# SpaceVNXInterface.net
KiCad netlist of a schematic drawn in Altium Designer
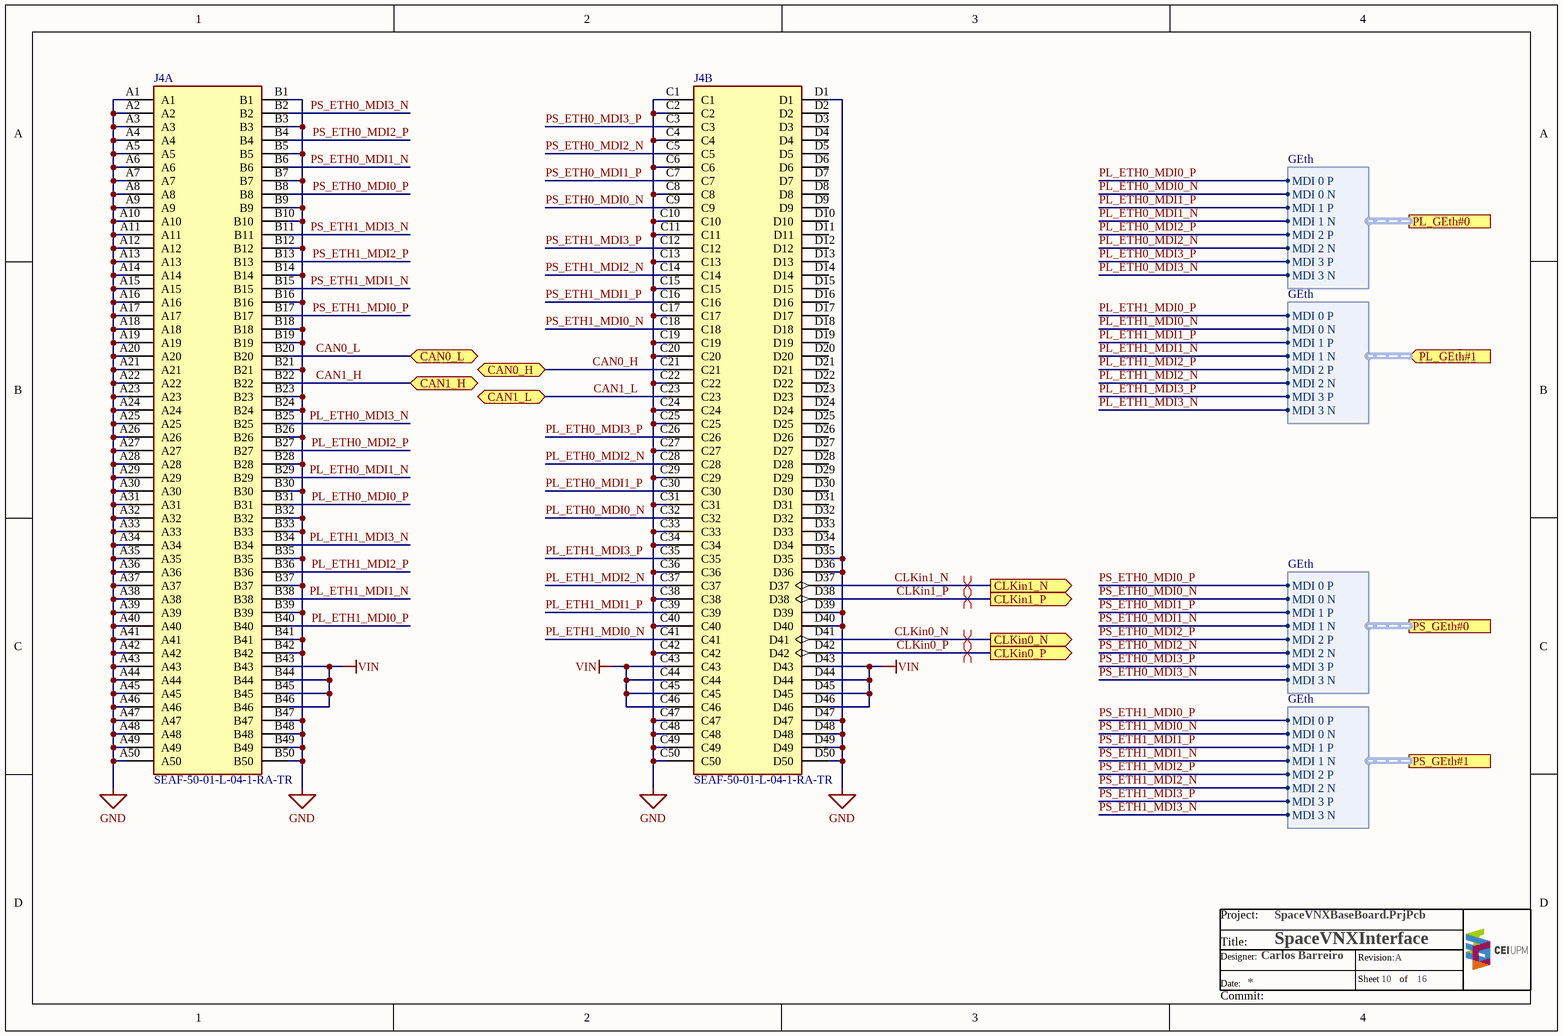
[diagram p0: SpaceVNXInterface.SchDoc]

(export (version "E")
  (design (tool "Eeschema 10.0.6"))
  (components
    (comp (ref "J4")
      (value "SEAF-50-01-L-04-1-RA-TR")
      (footprint "SAMTEC_SEAF-50-01-L-04-1-RA-TR")
      (libsource (lib "SpaceVNX") (part "SEAF-50-01-L-04-1-RA-TR"))
    )
  )
  (nets
    (net (code "2") (name "/CAN0_H") (class "Default")
      (node (ref "J4") (pin "C21") (pinfunction "C21_C21") (pintype "passive"))
    )
    (net (code "3") (name "/CAN0_L") (class "Default")
      (node (ref "J4") (pin "B20") (pinfunction "B20_B20") (pintype "passive"))
    )
    (net (code "4") (name "/CAN1_H") (class "Default")
      (node (ref "J4") (pin "B22") (pinfunction "B22_B22") (pintype "passive"))
    )
    (net (code "5") (name "/CAN1_L") (class "Default")
      (node (ref "J4") (pin "C23") (pinfunction "C23_C23") (pintype "passive"))
    )
    (net (code "6") (name "/CLKin0_N") (class "Default")
      (node (ref "J4") (pin "D41") (pinfunction "D41_D41") (pintype "passive"))
    )
    (net (code "7") (name "/CLKin0_P") (class "Default")
      (node (ref "J4") (pin "D42") (pinfunction "D42_D42") (pintype "passive"))
    )
    (net (code "8") (name "/CLKin1_N") (class "Default")
      (node (ref "J4") (pin "D37") (pinfunction "D37_D37") (pintype "passive"))
    )
    (net (code "9") (name "/CLKin1_P") (class "Default")
      (node (ref "J4") (pin "D38") (pinfunction "D38_D38") (pintype "passive"))
    )
    (net (code "10") (name "/PL_ETH0_MDI0_N") (class "Default")
      (node (ref "J4") (pin "C32") (pinfunction "C32_C32") (pintype "passive"))
    )
    (net (code "11") (name "/PL_ETH0_MDI0_P") (class "Default")
      (node (ref "J4") (pin "B31") (pinfunction "B31_B31") (pintype "passive"))
    )
    (net (code "12") (name "/PL_ETH0_MDI1_N") (class "Default")
      (node (ref "J4") (pin "B29") (pinfunction "B29_B29") (pintype "passive"))
    )
    (net (code "13") (name "/PL_ETH0_MDI1_P") (class "Default")
      (node (ref "J4") (pin "C30") (pinfunction "C30_C30") (pintype "passive"))
    )
    (net (code "14") (name "/PL_ETH0_MDI2_N") (class "Default")
      (node (ref "J4") (pin "C28") (pinfunction "C28_C28") (pintype "passive"))
    )
    (net (code "15") (name "/PL_ETH0_MDI2_P") (class "Default")
      (node (ref "J4") (pin "B27") (pinfunction "B27_B27") (pintype "passive"))
    )
    (net (code "16") (name "/PL_ETH0_MDI3_N") (class "Default")
      (node (ref "J4") (pin "B25") (pinfunction "B25_B25") (pintype "passive"))
    )
    (net (code "17") (name "/PL_ETH0_MDI3_P") (class "Default")
      (node (ref "J4") (pin "C26") (pinfunction "C26_C26") (pintype "passive"))
    )
    (net (code "18") (name "/PL_ETH1_MDI0_N") (class "Default")
      (node (ref "J4") (pin "C41") (pinfunction "C41_C41") (pintype "passive"))
    )
    (net (code "19") (name "/PL_ETH1_MDI0_P") (class "Default")
      (node (ref "J4") (pin "B40") (pinfunction "B40_B40") (pintype "passive"))
    )
    (net (code "20") (name "/PL_ETH1_MDI1_N") (class "Default")
      (node (ref "J4") (pin "B38") (pinfunction "B38_B38") (pintype "passive"))
    )
    (net (code "21") (name "/PL_ETH1_MDI1_P") (class "Default")
      (node (ref "J4") (pin "C39") (pinfunction "C39_C39") (pintype "passive"))
    )
    (net (code "22") (name "/PL_ETH1_MDI2_N") (class "Default")
      (node (ref "J4") (pin "C37") (pinfunction "C37_C37") (pintype "passive"))
    )
    (net (code "23") (name "/PL_ETH1_MDI2_P") (class "Default")
      (node (ref "J4") (pin "B36") (pinfunction "B36_B36") (pintype "passive"))
    )
    (net (code "24") (name "/PL_ETH1_MDI3_N") (class "Default")
      (node (ref "J4") (pin "B34") (pinfunction "B34_B34") (pintype "passive"))
    )
    (net (code "25") (name "/PL_ETH1_MDI3_P") (class "Default")
      (node (ref "J4") (pin "C35") (pinfunction "C35_C35") (pintype "passive"))
    )
    (net (code "26") (name "/PS_ETH0_MDI0_N") (class "Default")
      (node (ref "J4") (pin "C9") (pinfunction "C9_C9") (pintype "passive"))
    )
    (net (code "27") (name "/PS_ETH0_MDI0_P") (class "Default")
      (node (ref "J4") (pin "B8") (pinfunction "B8_B8") (pintype "passive"))
    )
    (net (code "28") (name "/PS_ETH0_MDI1_N") (class "Default")
      (node (ref "J4") (pin "B6") (pinfunction "B6_B6") (pintype "passive"))
    )
    (net (code "29") (name "/PS_ETH0_MDI1_P") (class "Default")
      (node (ref "J4") (pin "C7") (pinfunction "C7_C7") (pintype "passive"))
    )
    (net (code "30") (name "/PS_ETH0_MDI2_N") (class "Default")
      (node (ref "J4") (pin "C5") (pinfunction "C5_C5") (pintype "passive"))
    )
    (net (code "31") (name "/PS_ETH0_MDI2_P") (class "Default")
      (node (ref "J4") (pin "B4") (pinfunction "B4_B4") (pintype "passive"))
    )
    (net (code "32") (name "/PS_ETH0_MDI3_N") (class "Default")
      (node (ref "J4") (pin "B2") (pinfunction "B2_B2") (pintype "passive"))
    )
    (net (code "33") (name "/PS_ETH0_MDI3_P") (class "Default")
      (node (ref "J4") (pin "C3") (pinfunction "C3_C3") (pintype "passive"))
    )
    (net (code "34") (name "/PS_ETH1_MDI0_N") (class "Default")
      (node (ref "J4") (pin "C18") (pinfunction "C18_C18") (pintype "passive"))
    )
    (net (code "35") (name "/PS_ETH1_MDI0_P") (class "Default")
      (node (ref "J4") (pin "B17") (pinfunction "B17_B17") (pintype "passive"))
    )
    (net (code "36") (name "/PS_ETH1_MDI1_N") (class "Default")
      (node (ref "J4") (pin "B15") (pinfunction "B15_B15") (pintype "passive"))
    )
    (net (code "37") (name "/PS_ETH1_MDI1_P") (class "Default")
      (node (ref "J4") (pin "C16") (pinfunction "C16_C16") (pintype "passive"))
    )
    (net (code "38") (name "/PS_ETH1_MDI2_N") (class "Default")
      (node (ref "J4") (pin "C14") (pinfunction "C14_C14") (pintype "passive"))
    )
    (net (code "39") (name "/PS_ETH1_MDI2_P") (class "Default")
      (node (ref "J4") (pin "B13") (pinfunction "B13_B13") (pintype "passive"))
    )
    (net (code "40") (name "/PS_ETH1_MDI3_N") (class "Default")
      (node (ref "J4") (pin "B11") (pinfunction "B11_B11") (pintype "passive"))
    )
    (net (code "41") (name "/PS_ETH1_MDI3_P") (class "Default")
      (node (ref "J4") (pin "C12") (pinfunction "C12_C12") (pintype "passive"))
    )
    (net (code "43") (name "GND") (class "Default")
      (node (ref "J4") (pin "A1") (pinfunction "A1_A1") (pintype "passive"))
      (node (ref "J4") (pin "A10") (pinfunction "A10_A10") (pintype "passive"))
      (node (ref "J4") (pin "A11") (pinfunction "A11_A11") (pintype "passive"))
      (node (ref "J4") (pin "A12") (pinfunction "A12_A12") (pintype "passive"))
      (node (ref "J4") (pin "A13") (pinfunction "A13_A13") (pintype "passive"))
      (node (ref "J4") (pin "A14") (pinfunction "A14_A14") (pintype "passive"))
      (node (ref "J4") (pin "A15") (pinfunction "A15_A15") (pintype "passive"))
      (node (ref "J4") (pin "A16") (pinfunction "A16_A16") (pintype "passive"))
      (node (ref "J4") (pin "A17") (pinfunction "A17_A17") (pintype "passive"))
      (node (ref "J4") (pin "A18") (pinfunction "A18_A18") (pintype "passive"))
      (node (ref "J4") (pin "A19") (pinfunction "A19_A19") (pintype "passive"))
      (node (ref "J4") (pin "A2") (pinfunction "A2_A2") (pintype "passive"))
      (node (ref "J4") (pin "A20") (pinfunction "A20_A20") (pintype "passive"))
      (node (ref "J4") (pin "A21") (pinfunction "A21_A21") (pintype "passive"))
      (node (ref "J4") (pin "A22") (pinfunction "A22_A22") (pintype "passive"))
      (node (ref "J4") (pin "A23") (pinfunction "A23_A23") (pintype "passive"))
      (node (ref "J4") (pin "A24") (pinfunction "A24_A24") (pintype "passive"))
      (node (ref "J4") (pin "A25") (pinfunction "A25_A25") (pintype "passive"))
      (node (ref "J4") (pin "A26") (pinfunction "A26_A26") (pintype "passive"))
      (node (ref "J4") (pin "A27") (pinfunction "A27_A27") (pintype "passive"))
      (node (ref "J4") (pin "A28") (pinfunction "A28_A28") (pintype "passive"))
      (node (ref "J4") (pin "A29") (pinfunction "A29_A29") (pintype "passive"))
      (node (ref "J4") (pin "A3") (pinfunction "A3_A3") (pintype "passive"))
      (node (ref "J4") (pin "A30") (pinfunction "A30_A30") (pintype "passive"))
      (node (ref "J4") (pin "A31") (pinfunction "A31_A31") (pintype "passive"))
      (node (ref "J4") (pin "A32") (pinfunction "A32_A32") (pintype "passive"))
      (node (ref "J4") (pin "A33") (pinfunction "A33_A33") (pintype "passive"))
      (node (ref "J4") (pin "A34") (pinfunction "A34_A34") (pintype "passive"))
      (node (ref "J4") (pin "A35") (pinfunction "A35_A35") (pintype "passive"))
      (node (ref "J4") (pin "A36") (pinfunction "A36_A36") (pintype "passive"))
      (node (ref "J4") (pin "A37") (pinfunction "A37_A37") (pintype "passive"))
      (node (ref "J4") (pin "A38") (pinfunction "A38_A38") (pintype "passive"))
      (node (ref "J4") (pin "A39") (pinfunction "A39_A39") (pintype "passive"))
      (node (ref "J4") (pin "A4") (pinfunction "A4_A4") (pintype "passive"))
      (node (ref "J4") (pin "A40") (pinfunction "A40_A40") (pintype "passive"))
      (node (ref "J4") (pin "A41") (pinfunction "A41_A41") (pintype "passive"))
      (node (ref "J4") (pin "A42") (pinfunction "A42_A42") (pintype "passive"))
      (node (ref "J4") (pin "A43") (pinfunction "A43_A43") (pintype "passive"))
      (node (ref "J4") (pin "A44") (pinfunction "A44_A44") (pintype "passive"))
      (node (ref "J4") (pin "A45") (pinfunction "A45_A45") (pintype "passive"))
      (node (ref "J4") (pin "A46") (pinfunction "A46_A46") (pintype "passive"))
      (node (ref "J4") (pin "A47") (pinfunction "A47_A47") (pintype "passive"))
      (node (ref "J4") (pin "A48") (pinfunction "A48_A48") (pintype "passive"))
      (node (ref "J4") (pin "A49") (pinfunction "A49_A49") (pintype "passive"))
      (node (ref "J4") (pin "A5") (pinfunction "A5_A5") (pintype "passive"))
      (node (ref "J4") (pin "A50") (pinfunction "A50_A50") (pintype "passive"))
      (node (ref "J4") (pin "A6") (pinfunction "A6_A6") (pintype "passive"))
      (node (ref "J4") (pin "A7") (pinfunction "A7_A7") (pintype "passive"))
      (node (ref "J4") (pin "A8") (pinfunction "A8_A8") (pintype "passive"))
      (node (ref "J4") (pin "A9") (pinfunction "A9_A9") (pintype "passive"))
      (node (ref "J4") (pin "B1") (pinfunction "B1_B1") (pintype "passive"))
      (node (ref "J4") (pin "B10") (pinfunction "B10_B10") (pintype "passive"))
      (node (ref "J4") (pin "B12") (pinfunction "B12_B12") (pintype "passive"))
      (node (ref "J4") (pin "B14") (pinfunction "B14_B14") (pintype "passive"))
      (node (ref "J4") (pin "B16") (pinfunction "B16_B16") (pintype "passive"))
      (node (ref "J4") (pin "B18") (pinfunction "B18_B18") (pintype "passive"))
      (node (ref "J4") (pin "B19") (pinfunction "B19_B19") (pintype "passive"))
      (node (ref "J4") (pin "B21") (pinfunction "B21_B21") (pintype "passive"))
      (node (ref "J4") (pin "B23") (pinfunction "B23_B23") (pintype "passive"))
      (node (ref "J4") (pin "B24") (pinfunction "B24_B24") (pintype "passive"))
      (node (ref "J4") (pin "B26") (pinfunction "B26_B26") (pintype "passive"))
      (node (ref "J4") (pin "B28") (pinfunction "B28_B28") (pintype "passive"))
      (node (ref "J4") (pin "B3") (pinfunction "B3_B3") (pintype "passive"))
      (node (ref "J4") (pin "B30") (pinfunction "B30_B30") (pintype "passive"))
      (node (ref "J4") (pin "B32") (pinfunction "B32_B32") (pintype "passive"))
      (node (ref "J4") (pin "B33") (pinfunction "B33_B33") (pintype "passive"))
      (node (ref "J4") (pin "B35") (pinfunction "B35_B35") (pintype "passive"))
      (node (ref "J4") (pin "B37") (pinfunction "B37_B37") (pintype "passive"))
      (node (ref "J4") (pin "B39") (pinfunction "B39_B39") (pintype "passive"))
      (node (ref "J4") (pin "B41") (pinfunction "B41_B41") (pintype "passive"))
      (node (ref "J4") (pin "B42") (pinfunction "B42_B42") (pintype "passive"))
      (node (ref "J4") (pin "B47") (pinfunction "B47_B47") (pintype "passive"))
      (node (ref "J4") (pin "B48") (pinfunction "B48_B48") (pintype "passive"))
      (node (ref "J4") (pin "B49") (pinfunction "B49_B49") (pintype "passive"))
      (node (ref "J4") (pin "B5") (pinfunction "B5_B5") (pintype "passive"))
      (node (ref "J4") (pin "B50") (pinfunction "B50_B50") (pintype "passive"))
      (node (ref "J4") (pin "B7") (pinfunction "B7_B7") (pintype "passive"))
      (node (ref "J4") (pin "B9") (pinfunction "B9_B9") (pintype "passive"))
      (node (ref "J4") (pin "C1") (pinfunction "C1_C1") (pintype "passive"))
      (node (ref "J4") (pin "C10") (pinfunction "C10_C10") (pintype "passive"))
      (node (ref "J4") (pin "C11") (pinfunction "C11_C11") (pintype "passive"))
      (node (ref "J4") (pin "C13") (pinfunction "C13_C13") (pintype "passive"))
      (node (ref "J4") (pin "C15") (pinfunction "C15_C15") (pintype "passive"))
      (node (ref "J4") (pin "C17") (pinfunction "C17_C17") (pintype "passive"))
      (node (ref "J4") (pin "C19") (pinfunction "C19_C19") (pintype "passive"))
      (node (ref "J4") (pin "C2") (pinfunction "C2_C2") (pintype "passive"))
      (node (ref "J4") (pin "C20") (pinfunction "C20_C20") (pintype "passive"))
      (node (ref "J4") (pin "C22") (pinfunction "C22_C22") (pintype "passive"))
      (node (ref "J4") (pin "C24") (pinfunction "C24_C24") (pintype "passive"))
      (node (ref "J4") (pin "C25") (pinfunction "C25_C25") (pintype "passive"))
      (node (ref "J4") (pin "C27") (pinfunction "C27_C27") (pintype "passive"))
      (node (ref "J4") (pin "C29") (pinfunction "C29_C29") (pintype "passive"))
      (node (ref "J4") (pin "C31") (pinfunction "C31_C31") (pintype "passive"))
      (node (ref "J4") (pin "C33") (pinfunction "C33_C33") (pintype "passive"))
      (node (ref "J4") (pin "C34") (pinfunction "C34_C34") (pintype "passive"))
      (node (ref "J4") (pin "C36") (pinfunction "C36_C36") (pintype "passive"))
      (node (ref "J4") (pin "C38") (pinfunction "C38_C38") (pintype "passive"))
      (node (ref "J4") (pin "C4") (pinfunction "C4_C4") (pintype "passive"))
      (node (ref "J4") (pin "C40") (pinfunction "C40_C40") (pintype "passive"))
      (node (ref "J4") (pin "C42") (pinfunction "C42_C42") (pintype "passive"))
      (node (ref "J4") (pin "C47") (pinfunction "C47_C47") (pintype "passive"))
      (node (ref "J4") (pin "C48") (pinfunction "C48_C48") (pintype "passive"))
      (node (ref "J4") (pin "C49") (pinfunction "C49_C49") (pintype "passive"))
      (node (ref "J4") (pin "C50") (pinfunction "C50_C50") (pintype "passive"))
      (node (ref "J4") (pin "C6") (pinfunction "C6_C6") (pintype "passive"))
      (node (ref "J4") (pin "C8") (pinfunction "C8_C8") (pintype "passive"))
      (node (ref "J4") (pin "D1") (pinfunction "D1_D1") (pintype "passive"))
      (node (ref "J4") (pin "D35") (pinfunction "D35_D35") (pintype "passive"))
      (node (ref "J4") (pin "D36") (pinfunction "D36_D36") (pintype "passive"))
      (node (ref "J4") (pin "D39") (pinfunction "D39_D39") (pintype "passive"))
      (node (ref "J4") (pin "D40") (pinfunction "D40_D40") (pintype "passive"))
      (node (ref "J4") (pin "D47") (pinfunction "D47_D47") (pintype "passive"))
      (node (ref "J4") (pin "D48") (pinfunction "D48_D48") (pintype "passive"))
      (node (ref "J4") (pin "D49") (pinfunction "D49_D49") (pintype "passive"))
      (node (ref "J4") (pin "D50") (pinfunction "D50_D50") (pintype "passive"))
    )
    (net (code "44") (name "VIN") (class "Default")
      (node (ref "J4") (pin "B43") (pinfunction "B43_B43") (pintype "passive"))
      (node (ref "J4") (pin "B44") (pinfunction "B44_B44") (pintype "passive"))
      (node (ref "J4") (pin "B45") (pinfunction "B45_B45") (pintype "passive"))
      (node (ref "J4") (pin "B46") (pinfunction "B46_B46") (pintype "passive"))
      (node (ref "J4") (pin "C43") (pinfunction "C43_C43") (pintype "passive"))
      (node (ref "J4") (pin "C44") (pinfunction "C44_C44") (pintype "passive"))
      (node (ref "J4") (pin "C45") (pinfunction "C45_C45") (pintype "passive"))
      (node (ref "J4") (pin "C46") (pinfunction "C46_C46") (pintype "passive"))
      (node (ref "J4") (pin "D43") (pinfunction "D43_D43") (pintype "passive"))
      (node (ref "J4") (pin "D44") (pinfunction "D44_D44") (pintype "passive"))
      (node (ref "J4") (pin "D45") (pinfunction "D45_D45") (pintype "passive"))
      (node (ref "J4") (pin "D46") (pinfunction "D46_D46") (pintype "passive"))
    )
    (net (code "45") (name "unconnected-(J4-PadD2)") (class "Default")
      (node (ref "J4") (pin "D2") (pinfunction "D2_D2") (pintype "passive"))
    )
    (net (code "46") (name "unconnected-(J4-PadD3)") (class "Default")
      (node (ref "J4") (pin "D3") (pinfunction "D3_D3") (pintype "passive"))
    )
    (net (code "47") (name "unconnected-(J4-PadD4)") (class "Default")
      (node (ref "J4") (pin "D4") (pinfunction "D4_D4") (pintype "passive"))
    )
    (net (code "48") (name "unconnected-(J4-PadD5)") (class "Default")
      (node (ref "J4") (pin "D5") (pinfunction "D5_D5") (pintype "passive"))
    )
    (net (code "49") (name "unconnected-(J4-PadD6)") (class "Default")
      (node (ref "J4") (pin "D6") (pinfunction "D6_D6") (pintype "passive"))
    )
    (net (code "50") (name "unconnected-(J4-PadD7)") (class "Default")
      (node (ref "J4") (pin "D7") (pinfunction "D7_D7") (pintype "passive"))
    )
    (net (code "51") (name "unconnected-(J4-PadD8)") (class "Default")
      (node (ref "J4") (pin "D8") (pinfunction "D8_D8") (pintype "passive"))
    )
    (net (code "52") (name "unconnected-(J4-PadD9)") (class "Default")
      (node (ref "J4") (pin "D9") (pinfunction "D9_D9") (pintype "passive"))
    )
    (net (code "53") (name "unconnected-(J4-PadD10)") (class "Default")
      (node (ref "J4") (pin "D10") (pinfunction "D10_D10") (pintype "passive"))
    )
    (net (code "54") (name "unconnected-(J4-PadD11)") (class "Default")
      (node (ref "J4") (pin "D11") (pinfunction "D11_D11") (pintype "passive"))
    )
    (net (code "55") (name "unconnected-(J4-PadD12)") (class "Default")
      (node (ref "J4") (pin "D12") (pinfunction "D12_D12") (pintype "passive"))
    )
    (net (code "56") (name "unconnected-(J4-PadD13)") (class "Default")
      (node (ref "J4") (pin "D13") (pinfunction "D13_D13") (pintype "passive"))
    )
    (net (code "57") (name "unconnected-(J4-PadD14)") (class "Default")
      (node (ref "J4") (pin "D14") (pinfunction "D14_D14") (pintype "passive"))
    )
    (net (code "58") (name "unconnected-(J4-PadD15)") (class "Default")
      (node (ref "J4") (pin "D15") (pinfunction "D15_D15") (pintype "passive"))
    )
    (net (code "59") (name "unconnected-(J4-PadD16)") (class "Default")
      (node (ref "J4") (pin "D16") (pinfunction "D16_D16") (pintype "passive"))
    )
    (net (code "60") (name "unconnected-(J4-PadD17)") (class "Default")
      (node (ref "J4") (pin "D17") (pinfunction "D17_D17") (pintype "passive"))
    )
    (net (code "61") (name "unconnected-(J4-PadD18)") (class "Default")
      (node (ref "J4") (pin "D18") (pinfunction "D18_D18") (pintype "passive"))
    )
    (net (code "62") (name "unconnected-(J4-PadD19)") (class "Default")
      (node (ref "J4") (pin "D19") (pinfunction "D19_D19") (pintype "passive"))
    )
    (net (code "63") (name "unconnected-(J4-PadD20)") (class "Default")
      (node (ref "J4") (pin "D20") (pinfunction "D20_D20") (pintype "passive"))
    )
    (net (code "64") (name "unconnected-(J4-PadD21)") (class "Default")
      (node (ref "J4") (pin "D21") (pinfunction "D21_D21") (pintype "passive"))
    )
    (net (code "65") (name "unconnected-(J4-PadD22)") (class "Default")
      (node (ref "J4") (pin "D22") (pinfunction "D22_D22") (pintype "passive"))
    )
    (net (code "66") (name "unconnected-(J4-PadD23)") (class "Default")
      (node (ref "J4") (pin "D23") (pinfunction "D23_D23") (pintype "passive"))
    )
    (net (code "67") (name "unconnected-(J4-PadD24)") (class "Default")
      (node (ref "J4") (pin "D24") (pinfunction "D24_D24") (pintype "passive"))
    )
    (net (code "68") (name "unconnected-(J4-PadD25)") (class "Default")
      (node (ref "J4") (pin "D25") (pinfunction "D25_D25") (pintype "passive"))
    )
    (net (code "69") (name "unconnected-(J4-PadD26)") (class "Default")
      (node (ref "J4") (pin "D26") (pinfunction "D26_D26") (pintype "passive"))
    )
    (net (code "70") (name "unconnected-(J4-PadD27)") (class "Default")
      (node (ref "J4") (pin "D27") (pinfunction "D27_D27") (pintype "passive"))
    )
    (net (code "71") (name "unconnected-(J4-PadD28)") (class "Default")
      (node (ref "J4") (pin "D28") (pinfunction "D28_D28") (pintype "passive"))
    )
    (net (code "72") (name "unconnected-(J4-PadD29)") (class "Default")
      (node (ref "J4") (pin "D29") (pinfunction "D29_D29") (pintype "passive"))
    )
    (net (code "73") (name "unconnected-(J4-PadD30)") (class "Default")
      (node (ref "J4") (pin "D30") (pinfunction "D30_D30") (pintype "passive"))
    )
    (net (code "74") (name "unconnected-(J4-PadD31)") (class "Default")
      (node (ref "J4") (pin "D31") (pinfunction "D31_D31") (pintype "passive"))
    )
    (net (code "75") (name "unconnected-(J4-PadD32)") (class "Default")
      (node (ref "J4") (pin "D32") (pinfunction "D32_D32") (pintype "passive"))
    )
    (net (code "76") (name "unconnected-(J4-PadD33)") (class "Default")
      (node (ref "J4") (pin "D33") (pinfunction "D33_D33") (pintype "passive"))
    )
    (net (code "77") (name "unconnected-(J4-PadD34)") (class "Default")
      (node (ref "J4") (pin "D34") (pinfunction "D34_D34") (pintype "passive"))
    )
  )
)
